# Interconnect_board.net
KiCad netlist of a schematic drawn in EAGLE
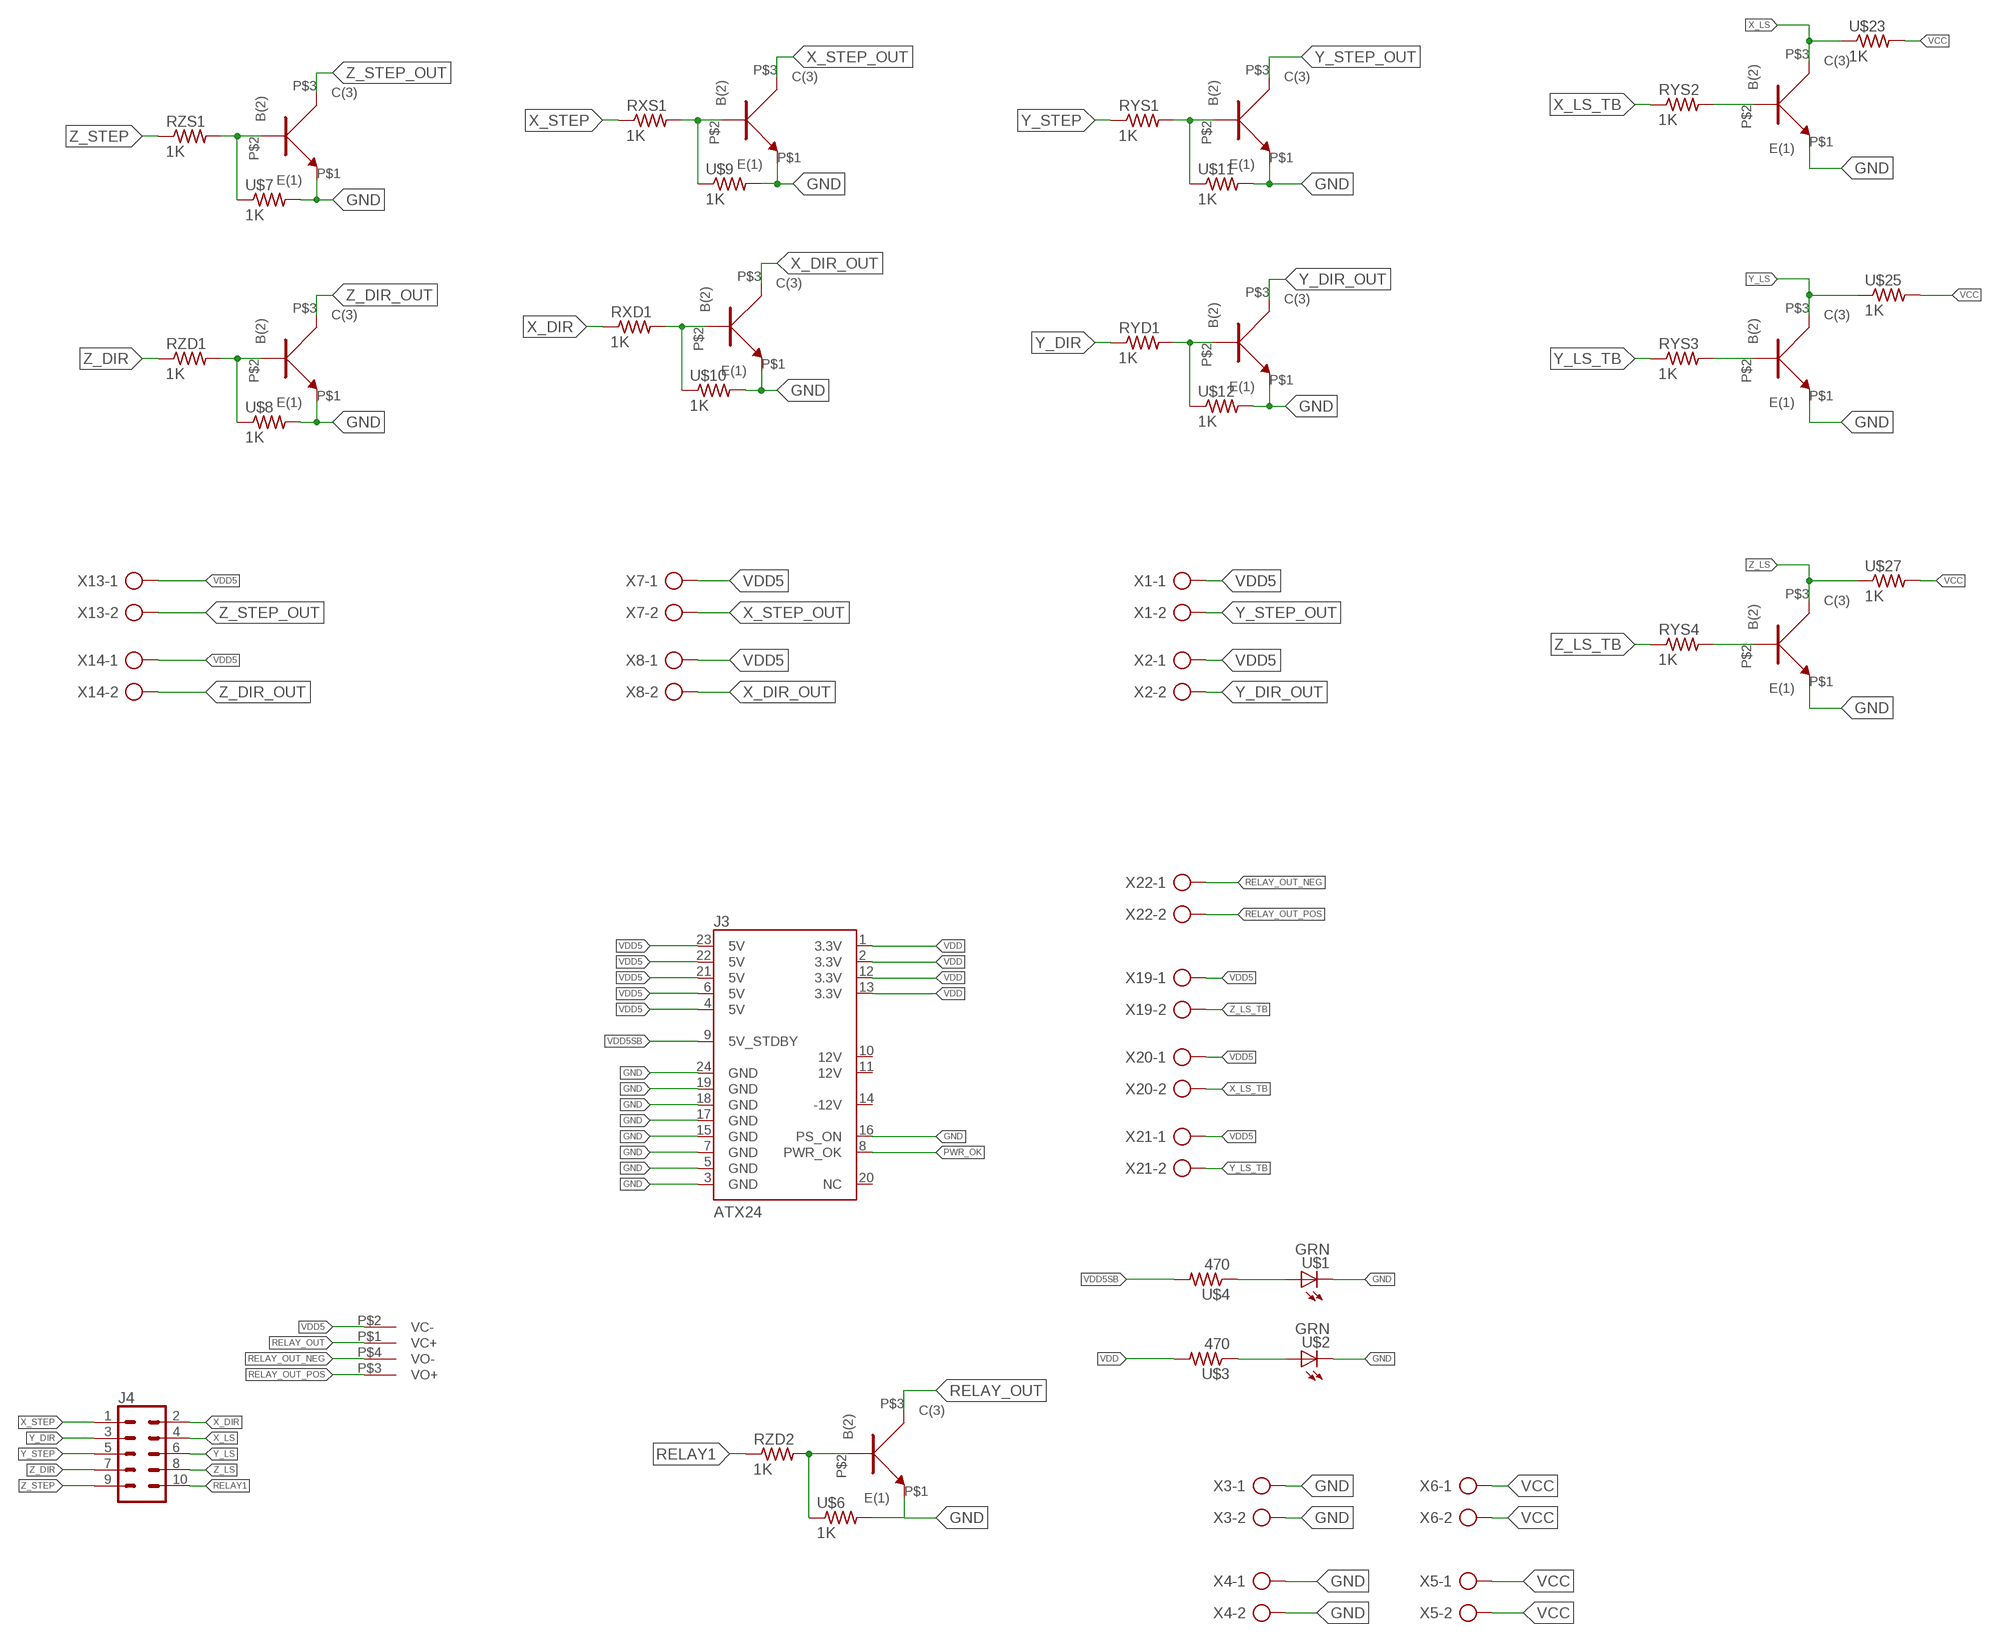
[diagram p0: schematic, sheet 1]

(export (version "E")
  (design (tool "Eeschema 10.0.6"))
  (components
    (comp (ref "J3")
      (value "ATX24")
      (footprint "eagle-import:ATX24_STRAIGHT")
      (libsource (lib "eagle-import") (part "ATX24"))
    )
    (comp (ref "J4")
      (value "CONN_05X2SHD")
      (footprint "eagle-import:2X5-SHROUDED")
      (libsource (lib "eagle-import") (part "CONN_05X2SHD"))
    )
    (comp (ref "RXD1")
      (value "R_0805_1K")
      (footprint "eagle-import:R_0805_1K")
      (libsource (lib "eagle-import") (part "R_0805_1K"))
    )
    (comp (ref "RXS1")
      (value "R_0805_1K")
      (footprint "eagle-import:R_0805_1K")
      (libsource (lib "eagle-import") (part "R_0805_1K"))
    )
    (comp (ref "RYD1")
      (value "R_0805_1K")
      (footprint "eagle-import:R_0805_1K")
      (libsource (lib "eagle-import") (part "R_0805_1K"))
    )
    (comp (ref "RYS1")
      (value "R_0805_1K")
      (footprint "eagle-import:R_0805_1K")
      (libsource (lib "eagle-import") (part "R_0805_1K"))
    )
    (comp (ref "RYS2")
      (value "R_0805_1K")
      (footprint "eagle-import:R_0805_1K")
      (libsource (lib "eagle-import") (part "R_0805_1K"))
    )
    (comp (ref "RYS3")
      (value "R_0805_1K")
      (footprint "eagle-import:R_0805_1K")
      (libsource (lib "eagle-import") (part "R_0805_1K"))
    )
    (comp (ref "RYS4")
      (value "R_0805_1K")
      (footprint "eagle-import:R_0805_1K")
      (libsource (lib "eagle-import") (part "R_0805_1K"))
    )
    (comp (ref "RZD1")
      (value "R_0805_1K")
      (footprint "eagle-import:R_0805_1K")
      (libsource (lib "eagle-import") (part "R_0805_1K"))
    )
    (comp (ref "RZD2")
      (value "R_0805_1K")
      (footprint "eagle-import:R_0805_1K")
      (libsource (lib "eagle-import") (part "R_0805_1K"))
    )
    (comp (ref "RZS1")
      (value "R_0805_1K")
      (footprint "eagle-import:R_0805_1K")
      (libsource (lib "eagle-import") (part "R_0805_1K"))
    )
    (comp (ref "U$1")
      (value "LED_0805_GREEN")
      (footprint "eagle-import:LED_0805_GREEN")
      (libsource (lib "eagle-import") (part "LED_0805_GREEN"))
    )
    (comp (ref "U$2")
      (value "LED_0805_GREEN")
      (footprint "eagle-import:LED_0805_GREEN")
      (libsource (lib "eagle-import") (part "LED_0805_GREEN"))
    )
    (comp (ref "U$3")
      (value "R_0805_470")
      (footprint "eagle-import:R_0805_470")
      (libsource (lib "eagle-import") (part "R_0805_470"))
    )
    (comp (ref "U$4")
      (value "R_0805_470")
      (footprint "eagle-import:R_0805_470")
      (libsource (lib "eagle-import") (part "R_0805_470"))
    )
    (comp (ref "U$5")
      (value "RELAY_KYOTO_KF0604D")
      (footprint "eagle-import:RELAY_KYOTO_KF0604D")
      (libsource (lib "eagle-import") (part "RELAY_KYOTO_KF0604D"))
    )
    (comp (ref "U$6")
      (value "R_0805_1K")
      (footprint "eagle-import:R_0805_1K")
      (libsource (lib "eagle-import") (part "R_0805_1K"))
    )
    (comp (ref "U$7")
      (value "R_0805_1K")
      (footprint "eagle-import:R_0805_1K")
      (libsource (lib "eagle-import") (part "R_0805_1K"))
    )
    (comp (ref "U$8")
      (value "R_0805_1K")
      (footprint "eagle-import:R_0805_1K")
      (libsource (lib "eagle-import") (part "R_0805_1K"))
    )
    (comp (ref "U$9")
      (value "R_0805_1K")
      (footprint "eagle-import:R_0805_1K")
      (libsource (lib "eagle-import") (part "R_0805_1K"))
    )
    (comp (ref "U$10")
      (value "R_0805_1K")
      (footprint "eagle-import:R_0805_1K")
      (libsource (lib "eagle-import") (part "R_0805_1K"))
    )
    (comp (ref "U$11")
      (value "R_0805_1K")
      (footprint "eagle-import:R_0805_1K")
      (libsource (lib "eagle-import") (part "R_0805_1K"))
    )
    (comp (ref "U$12")
      (value "R_0805_1K")
      (footprint "eagle-import:R_0805_1K")
      (libsource (lib "eagle-import") (part "R_0805_1K"))
    )
    (comp (ref "U$13")
      (value "TRANS_NPN")
      (footprint "eagle-import:TO_92_STRAIGHT")
      (libsource (lib "eagle-import") (part "TRANS_NPN"))
    )
    (comp (ref "U$14")
      (value "TRANS_NPN")
      (footprint "eagle-import:TO_92_STRAIGHT")
      (libsource (lib "eagle-import") (part "TRANS_NPN"))
    )
    (comp (ref "U$15")
      (value "TRANS_NPN")
      (footprint "eagle-import:TO_92_STRAIGHT")
      (libsource (lib "eagle-import") (part "TRANS_NPN"))
    )
    (comp (ref "U$16")
      (value "TRANS_NPN")
      (footprint "eagle-import:TO_92_STRAIGHT")
      (libsource (lib "eagle-import") (part "TRANS_NPN"))
    )
    (comp (ref "U$17")
      (value "TRANS_NPN")
      (footprint "eagle-import:TO_92_STRAIGHT")
      (libsource (lib "eagle-import") (part "TRANS_NPN"))
    )
    (comp (ref "U$18")
      (value "TRANS_NPN")
      (footprint "eagle-import:TO_92_STRAIGHT")
      (libsource (lib "eagle-import") (part "TRANS_NPN"))
    )
    (comp (ref "U$19")
      (value "TRANS_NPN")
      (footprint "eagle-import:TO_92_STRAIGHT")
      (libsource (lib "eagle-import") (part "TRANS_NPN"))
    )
    (comp (ref "U$23")
      (value "R_0805_1K")
      (footprint "eagle-import:R_0805_1K")
      (libsource (lib "eagle-import") (part "R_0805_1K"))
    )
    (comp (ref "U$24")
      (value "TRANS_NPN")
      (footprint "eagle-import:TO_92_STRAIGHT")
      (libsource (lib "eagle-import") (part "TRANS_NPN"))
    )
    (comp (ref "U$25")
      (value "R_0805_1K")
      (footprint "eagle-import:R_0805_1K")
      (libsource (lib "eagle-import") (part "R_0805_1K"))
    )
    (comp (ref "U$26")
      (value "TRANS_NPN")
      (footprint "eagle-import:TO_92_STRAIGHT")
      (libsource (lib "eagle-import") (part "TRANS_NPN"))
    )
    (comp (ref "U$27")
      (value "R_0805_1K")
      (footprint "eagle-import:R_0805_1K")
      (libsource (lib "eagle-import") (part "R_0805_1K"))
    )
    (comp (ref "U$28")
      (value "TRANS_NPN")
      (footprint "eagle-import:TO_92_STRAIGHT")
      (libsource (lib "eagle-import") (part "TRANS_NPN"))
    )
    (comp (ref "X1")
      (value "AK300/2")
      (footprint "eagle-import:AK300_2")
      (libsource (lib "eagle-import") (part "AK300/2"))
    )
    (comp (ref "X2")
      (value "AK300/2")
      (footprint "eagle-import:AK300_2")
      (libsource (lib "eagle-import") (part "AK300/2"))
    )
    (comp (ref "X3")
      (value "AK300/2")
      (footprint "eagle-import:AK300_2")
      (libsource (lib "eagle-import") (part "AK300/2"))
    )
    (comp (ref "X4")
      (value "AK300/2")
      (footprint "eagle-import:AK300_2")
      (libsource (lib "eagle-import") (part "AK300/2"))
    )
    (comp (ref "X5")
      (value "AK300/2")
      (footprint "eagle-import:AK300_2")
      (libsource (lib "eagle-import") (part "AK300/2"))
    )
    (comp (ref "X6")
      (value "AK300/2")
      (footprint "eagle-import:AK300_2")
      (libsource (lib "eagle-import") (part "AK300/2"))
    )
    (comp (ref "X7")
      (value "AK300/2")
      (footprint "eagle-import:AK300_2")
      (libsource (lib "eagle-import") (part "AK300/2"))
    )
    (comp (ref "X8")
      (value "AK300/2")
      (footprint "eagle-import:AK300_2")
      (libsource (lib "eagle-import") (part "AK300/2"))
    )
    (comp (ref "X13")
      (value "AK300/2")
      (footprint "eagle-import:AK300_2")
      (libsource (lib "eagle-import") (part "AK300/2"))
    )
    (comp (ref "X14")
      (value "AK300/2")
      (footprint "eagle-import:AK300_2")
      (libsource (lib "eagle-import") (part "AK300/2"))
    )
    (comp (ref "X19")
      (value "AK300/2")
      (footprint "eagle-import:AK300_2")
      (libsource (lib "eagle-import") (part "AK300/2"))
    )
    (comp (ref "X20")
      (value "AK300/2")
      (footprint "eagle-import:AK300_2")
      (libsource (lib "eagle-import") (part "AK300/2"))
    )
    (comp (ref "X21")
      (value "AK300/2")
      (footprint "eagle-import:AK300_2")
      (libsource (lib "eagle-import") (part "AK300/2"))
    )
    (comp (ref "X22")
      (value "AK300/2")
      (footprint "eagle-import:AK300_2")
      (libsource (lib "eagle-import") (part "AK300/2"))
    )
  )
  (nets
    (net (code "1") (name "GND") (class "Default")
      (node (ref "J3") (pin "15") (pinfunction "GND_15") (pintype "bidirectional"))
      (node (ref "J3") (pin "16") (pinfunction "PS_ON_16") (pintype "bidirectional"))
      (node (ref "J3") (pin "17") (pinfunction "GND_17") (pintype "bidirectional"))
      (node (ref "J3") (pin "18") (pinfunction "GND_18") (pintype "bidirectional"))
      (node (ref "J3") (pin "19") (pinfunction "GND_19") (pintype "bidirectional"))
      (node (ref "J3") (pin "24") (pinfunction "GND_24") (pintype "bidirectional"))
      (node (ref "J3") (pin "3") (pinfunction "GND_3") (pintype "bidirectional"))
      (node (ref "J3") (pin "5") (pinfunction "GND_5") (pintype "bidirectional"))
      (node (ref "J3") (pin "7") (pinfunction "GND_7") (pintype "bidirectional"))
      (node (ref "U$1") (pin "C") (pinfunction "C_C") (pintype "passive"))
      (node (ref "U$10") (pin "2") (pinfunction "2_2") (pintype "passive"))
      (node (ref "U$11") (pin "2") (pinfunction "2_2") (pintype "passive"))
      (node (ref "U$12") (pin "2") (pinfunction "2_2") (pintype "passive"))
      (node (ref "U$13") (pin "P$1") (pinfunction "E(1)_P$1") (pintype "output"))
      (node (ref "U$14") (pin "P$1") (pinfunction "E(1)_P$1") (pintype "output"))
      (node (ref "U$15") (pin "P$1") (pinfunction "E(1)_P$1") (pintype "output"))
      (node (ref "U$16") (pin "P$1") (pinfunction "E(1)_P$1") (pintype "output"))
      (node (ref "U$17") (pin "P$1") (pinfunction "E(1)_P$1") (pintype "output"))
      (node (ref "U$18") (pin "P$1") (pinfunction "E(1)_P$1") (pintype "output"))
      (node (ref "U$19") (pin "P$1") (pinfunction "E(1)_P$1") (pintype "output"))
      (node (ref "U$2") (pin "C") (pinfunction "C_C") (pintype "passive"))
      (node (ref "U$24") (pin "P$1") (pinfunction "E(1)_P$1") (pintype "output"))
      (node (ref "U$26") (pin "P$1") (pinfunction "E(1)_P$1") (pintype "output"))
      (node (ref "U$28") (pin "P$1") (pinfunction "E(1)_P$1") (pintype "output"))
      (node (ref "U$6") (pin "2") (pinfunction "2_2") (pintype "passive"))
      (node (ref "U$7") (pin "2") (pinfunction "2_2") (pintype "passive"))
      (node (ref "U$8") (pin "2") (pinfunction "2_2") (pintype "passive"))
      (node (ref "U$9") (pin "2") (pinfunction "2_2") (pintype "passive"))
      (node (ref "X3") (pin "1") (pinfunction "KL_1") (pintype "passive"))
      (node (ref "X3") (pin "2") (pinfunction "KL_2") (pintype "passive"))
      (node (ref "X4") (pin "1") (pinfunction "KL_1") (pintype "passive"))
      (node (ref "X4") (pin "2") (pinfunction "KL_2") (pintype "passive"))
    )
    (net (code "2") (name "Net-(U$1-PadA)") (class "Default")
      (node (ref "U$1") (pin "A") (pinfunction "A_A") (pintype "passive"))
      (node (ref "U$4") (pin "1") (pinfunction "1_1") (pintype "passive"))
    )
    (net (code "3") (name "Net-(U$2-PadA)") (class "Default")
      (node (ref "U$2") (pin "A") (pinfunction "A_A") (pintype "passive"))
      (node (ref "U$3") (pin "1") (pinfunction "1_1") (pintype "passive"))
    )
    (net (code "4") (name "Net-(U$13-B(2))") (class "Default")
      (node (ref "RZS1") (pin "2") (pinfunction "2_2") (pintype "passive"))
      (node (ref "U$13") (pin "P$2") (pinfunction "B(2)_P$2") (pintype "input"))
      (node (ref "U$7") (pin "1") (pinfunction "1_1") (pintype "passive"))
    )
    (net (code "5") (name "Net-(U$14-B(2))") (class "Default")
      (node (ref "RZD1") (pin "2") (pinfunction "2_2") (pintype "passive"))
      (node (ref "U$14") (pin "P$2") (pinfunction "B(2)_P$2") (pintype "input"))
      (node (ref "U$8") (pin "1") (pinfunction "1_1") (pintype "passive"))
    )
    (net (code "6") (name "Net-(U$15-B(2))") (class "Default")
      (node (ref "RXS1") (pin "2") (pinfunction "2_2") (pintype "passive"))
      (node (ref "U$15") (pin "P$2") (pinfunction "B(2)_P$2") (pintype "input"))
      (node (ref "U$9") (pin "1") (pinfunction "1_1") (pintype "passive"))
    )
    (net (code "7") (name "Net-(U$16-B(2))") (class "Default")
      (node (ref "RXD1") (pin "2") (pinfunction "2_2") (pintype "passive"))
      (node (ref "U$10") (pin "1") (pinfunction "1_1") (pintype "passive"))
      (node (ref "U$16") (pin "P$2") (pinfunction "B(2)_P$2") (pintype "input"))
    )
    (net (code "8") (name "Net-(U$17-B(2))") (class "Default")
      (node (ref "RYD1") (pin "2") (pinfunction "2_2") (pintype "passive"))
      (node (ref "U$12") (pin "1") (pinfunction "1_1") (pintype "passive"))
      (node (ref "U$17") (pin "P$2") (pinfunction "B(2)_P$2") (pintype "input"))
    )
    (net (code "9") (name "Net-(U$18-B(2))") (class "Default")
      (node (ref "RYS1") (pin "2") (pinfunction "2_2") (pintype "passive"))
      (node (ref "U$11") (pin "1") (pinfunction "1_1") (pintype "passive"))
      (node (ref "U$18") (pin "P$2") (pinfunction "B(2)_P$2") (pintype "input"))
    )
    (net (code "10") (name "Net-(U$19-B(2))") (class "Default")
      (node (ref "RZD2") (pin "2") (pinfunction "2_2") (pintype "passive"))
      (node (ref "U$19") (pin "P$2") (pinfunction "B(2)_P$2") (pintype "input"))
      (node (ref "U$6") (pin "1") (pinfunction "1_1") (pintype "passive"))
    )
    (net (code "11") (name "Net-(U$24-B(2))") (class "Default")
      (node (ref "RYS2") (pin "2") (pinfunction "2_2") (pintype "passive"))
      (node (ref "U$24") (pin "P$2") (pinfunction "B(2)_P$2") (pintype "input"))
    )
    (net (code "12") (name "Net-(U$26-B(2))") (class "Default")
      (node (ref "RYS3") (pin "2") (pinfunction "2_2") (pintype "passive"))
      (node (ref "U$26") (pin "P$2") (pinfunction "B(2)_P$2") (pintype "input"))
    )
    (net (code "13") (name "Net-(U$28-B(2))") (class "Default")
      (node (ref "RYS4") (pin "2") (pinfunction "2_2") (pintype "passive"))
      (node (ref "U$28") (pin "P$2") (pinfunction "B(2)_P$2") (pintype "input"))
    )
    (net (code "14") (name "PWR_OK") (class "Default")
      (node (ref "J3") (pin "8") (pinfunction "PWR_OK_8") (pintype "bidirectional"))
    )
    (net (code "15") (name "RELAY1") (class "Default")
      (node (ref "J4") (pin "10") (pinfunction "10_10") (pintype "passive"))
      (node (ref "RZD2") (pin "1") (pinfunction "1_1") (pintype "passive"))
    )
    (net (code "16") (name "RELAY_OUT") (class "Default")
      (node (ref "U$19") (pin "P$3") (pinfunction "C(3)_P$3") (pintype "input"))
      (node (ref "U$5") (pin "P$1") (pinfunction "VC+_P$1") (pintype "bidirectional"))
    )
    (net (code "17") (name "RELAY_OUT_NEG") (class "Default")
      (node (ref "U$5") (pin "P$4") (pinfunction "VO-_P$4") (pintype "bidirectional"))
      (node (ref "X22") (pin "1") (pinfunction "KL_1") (pintype "passive"))
    )
    (net (code "18") (name "RELAY_OUT_POS") (class "Default")
      (node (ref "U$5") (pin "P$3") (pinfunction "VO+_P$3") (pintype "bidirectional"))
      (node (ref "X22") (pin "2") (pinfunction "KL_2") (pintype "passive"))
    )
    (net (code "19") (name "VCC") (class "Default")
      (node (ref "U$23") (pin "2") (pinfunction "2_2") (pintype "passive"))
      (node (ref "U$25") (pin "2") (pinfunction "2_2") (pintype "passive"))
      (node (ref "U$27") (pin "2") (pinfunction "2_2") (pintype "passive"))
      (node (ref "X5") (pin "1") (pinfunction "KL_1") (pintype "passive"))
      (node (ref "X5") (pin "2") (pinfunction "KL_2") (pintype "passive"))
      (node (ref "X6") (pin "1") (pinfunction "KL_1") (pintype "passive"))
      (node (ref "X6") (pin "2") (pinfunction "KL_2") (pintype "passive"))
    )
    (net (code "20") (name "VDD") (class "Default")
      (node (ref "J3") (pin "1") (pinfunction "3.3V_1") (pintype "bidirectional"))
      (node (ref "J3") (pin "12") (pinfunction "3.3V_12") (pintype "bidirectional"))
      (node (ref "J3") (pin "13") (pinfunction "3.3V_13") (pintype "bidirectional"))
      (node (ref "J3") (pin "2") (pinfunction "3.3V_2") (pintype "bidirectional"))
      (node (ref "U$3") (pin "2") (pinfunction "2_2") (pintype "passive"))
    )
    (net (code "21") (name "VDD5") (class "Default")
      (node (ref "J3") (pin "21") (pinfunction "5V_21") (pintype "bidirectional"))
      (node (ref "J3") (pin "22") (pinfunction "5V_22") (pintype "bidirectional"))
      (node (ref "J3") (pin "23") (pinfunction "5V_23") (pintype "bidirectional"))
      (node (ref "J3") (pin "4") (pinfunction "5V_4") (pintype "bidirectional"))
      (node (ref "J3") (pin "6") (pinfunction "5V_6") (pintype "bidirectional"))
      (node (ref "U$5") (pin "P$2") (pinfunction "VC-_P$2") (pintype "bidirectional"))
      (node (ref "X1") (pin "1") (pinfunction "KL_1") (pintype "passive"))
      (node (ref "X13") (pin "1") (pinfunction "KL_1") (pintype "passive"))
      (node (ref "X14") (pin "1") (pinfunction "KL_1") (pintype "passive"))
      (node (ref "X19") (pin "1") (pinfunction "KL_1") (pintype "passive"))
      (node (ref "X2") (pin "1") (pinfunction "KL_1") (pintype "passive"))
      (node (ref "X20") (pin "1") (pinfunction "KL_1") (pintype "passive"))
      (node (ref "X21") (pin "1") (pinfunction "KL_1") (pintype "passive"))
      (node (ref "X7") (pin "1") (pinfunction "KL_1") (pintype "passive"))
      (node (ref "X8") (pin "1") (pinfunction "KL_1") (pintype "passive"))
    )
    (net (code "22") (name "VDD5SB") (class "Default")
      (node (ref "J3") (pin "9") (pinfunction "5V_STDBY_9") (pintype "bidirectional"))
      (node (ref "U$4") (pin "2") (pinfunction "2_2") (pintype "passive"))
    )
    (net (code "23") (name "X_DIR") (class "Default")
      (node (ref "J4") (pin "2") (pinfunction "2_2") (pintype "passive"))
      (node (ref "RXD1") (pin "1") (pinfunction "1_1") (pintype "passive"))
    )
    (net (code "24") (name "X_DIR_OUT") (class "Default")
      (node (ref "U$16") (pin "P$3") (pinfunction "C(3)_P$3") (pintype "input"))
      (node (ref "X8") (pin "2") (pinfunction "KL_2") (pintype "passive"))
    )
    (net (code "25") (name "X_LS") (class "Default")
      (node (ref "J4") (pin "4") (pinfunction "4_4") (pintype "passive"))
      (node (ref "U$23") (pin "1") (pinfunction "1_1") (pintype "passive"))
      (node (ref "U$24") (pin "P$3") (pinfunction "C(3)_P$3") (pintype "input"))
    )
    (net (code "26") (name "X_LS_TB") (class "Default")
      (node (ref "RYS2") (pin "1") (pinfunction "1_1") (pintype "passive"))
      (node (ref "X20") (pin "2") (pinfunction "KL_2") (pintype "passive"))
    )
    (net (code "27") (name "X_STEP") (class "Default")
      (node (ref "J4") (pin "1") (pinfunction "1_1") (pintype "passive"))
      (node (ref "RXS1") (pin "1") (pinfunction "1_1") (pintype "passive"))
    )
    (net (code "28") (name "X_STEP_OUT") (class "Default")
      (node (ref "U$15") (pin "P$3") (pinfunction "C(3)_P$3") (pintype "input"))
      (node (ref "X7") (pin "2") (pinfunction "KL_2") (pintype "passive"))
    )
    (net (code "29") (name "Y_DIR") (class "Default")
      (node (ref "J4") (pin "3") (pinfunction "3_3") (pintype "passive"))
      (node (ref "RYD1") (pin "1") (pinfunction "1_1") (pintype "passive"))
    )
    (net (code "30") (name "Y_DIR_OUT") (class "Default")
      (node (ref "U$17") (pin "P$3") (pinfunction "C(3)_P$3") (pintype "input"))
      (node (ref "X2") (pin "2") (pinfunction "KL_2") (pintype "passive"))
    )
    (net (code "31") (name "Y_LS") (class "Default")
      (node (ref "J4") (pin "6") (pinfunction "6_6") (pintype "passive"))
      (node (ref "U$25") (pin "1") (pinfunction "1_1") (pintype "passive"))
      (node (ref "U$26") (pin "P$3") (pinfunction "C(3)_P$3") (pintype "input"))
    )
    (net (code "32") (name "Y_LS_TB") (class "Default")
      (node (ref "RYS3") (pin "1") (pinfunction "1_1") (pintype "passive"))
      (node (ref "X21") (pin "2") (pinfunction "KL_2") (pintype "passive"))
    )
    (net (code "33") (name "Y_STEP") (class "Default")
      (node (ref "J4") (pin "5") (pinfunction "5_5") (pintype "passive"))
      (node (ref "RYS1") (pin "1") (pinfunction "1_1") (pintype "passive"))
    )
    (net (code "34") (name "Y_STEP_OUT") (class "Default")
      (node (ref "U$18") (pin "P$3") (pinfunction "C(3)_P$3") (pintype "input"))
      (node (ref "X1") (pin "2") (pinfunction "KL_2") (pintype "passive"))
    )
    (net (code "35") (name "Z_DIR") (class "Default")
      (node (ref "J4") (pin "7") (pinfunction "7_7") (pintype "passive"))
      (node (ref "RZD1") (pin "1") (pinfunction "1_1") (pintype "passive"))
    )
    (net (code "36") (name "Z_DIR_OUT") (class "Default")
      (node (ref "U$14") (pin "P$3") (pinfunction "C(3)_P$3") (pintype "input"))
      (node (ref "X14") (pin "2") (pinfunction "KL_2") (pintype "passive"))
    )
    (net (code "37") (name "Z_LS") (class "Default")
      (node (ref "J4") (pin "8") (pinfunction "8_8") (pintype "passive"))
      (node (ref "U$27") (pin "1") (pinfunction "1_1") (pintype "passive"))
      (node (ref "U$28") (pin "P$3") (pinfunction "C(3)_P$3") (pintype "input"))
    )
    (net (code "38") (name "Z_LS_TB") (class "Default")
      (node (ref "RYS4") (pin "1") (pinfunction "1_1") (pintype "passive"))
      (node (ref "X19") (pin "2") (pinfunction "KL_2") (pintype "passive"))
    )
    (net (code "39") (name "Z_STEP") (class "Default")
      (node (ref "J4") (pin "9") (pinfunction "9_9") (pintype "passive"))
      (node (ref "RZS1") (pin "1") (pinfunction "1_1") (pintype "passive"))
    )
    (net (code "40") (name "Z_STEP_OUT") (class "Default")
      (node (ref "U$13") (pin "P$3") (pinfunction "C(3)_P$3") (pintype "input"))
      (node (ref "X13") (pin "2") (pinfunction "KL_2") (pintype "passive"))
    )
    (net (code "41") (name "unconnected-(J3--12V-Pad14)") (class "Default")
      (node (ref "J3") (pin "14") (pinfunction "-12V_14") (pintype "bidirectional"))
    )
    (net (code "42") (name "unconnected-(J3-12V-Pad10)") (class "Default")
      (node (ref "J3") (pin "10") (pinfunction "12V_10") (pintype "bidirectional"))
    )
    (net (code "43") (name "unconnected-(J3-12V-Pad11)") (class "Default")
      (node (ref "J3") (pin "11") (pinfunction "12V_11") (pintype "bidirectional"))
    )
    (net (code "44") (name "unconnected-(J3-NC-Pad20)") (class "Default")
      (node (ref "J3") (pin "20") (pinfunction "NC_20") (pintype "bidirectional"))
    )
  )
)
